# ProProject__led_2025-12-18.net
KiCad netlist of a schematic drawn in EasyEDA Pro
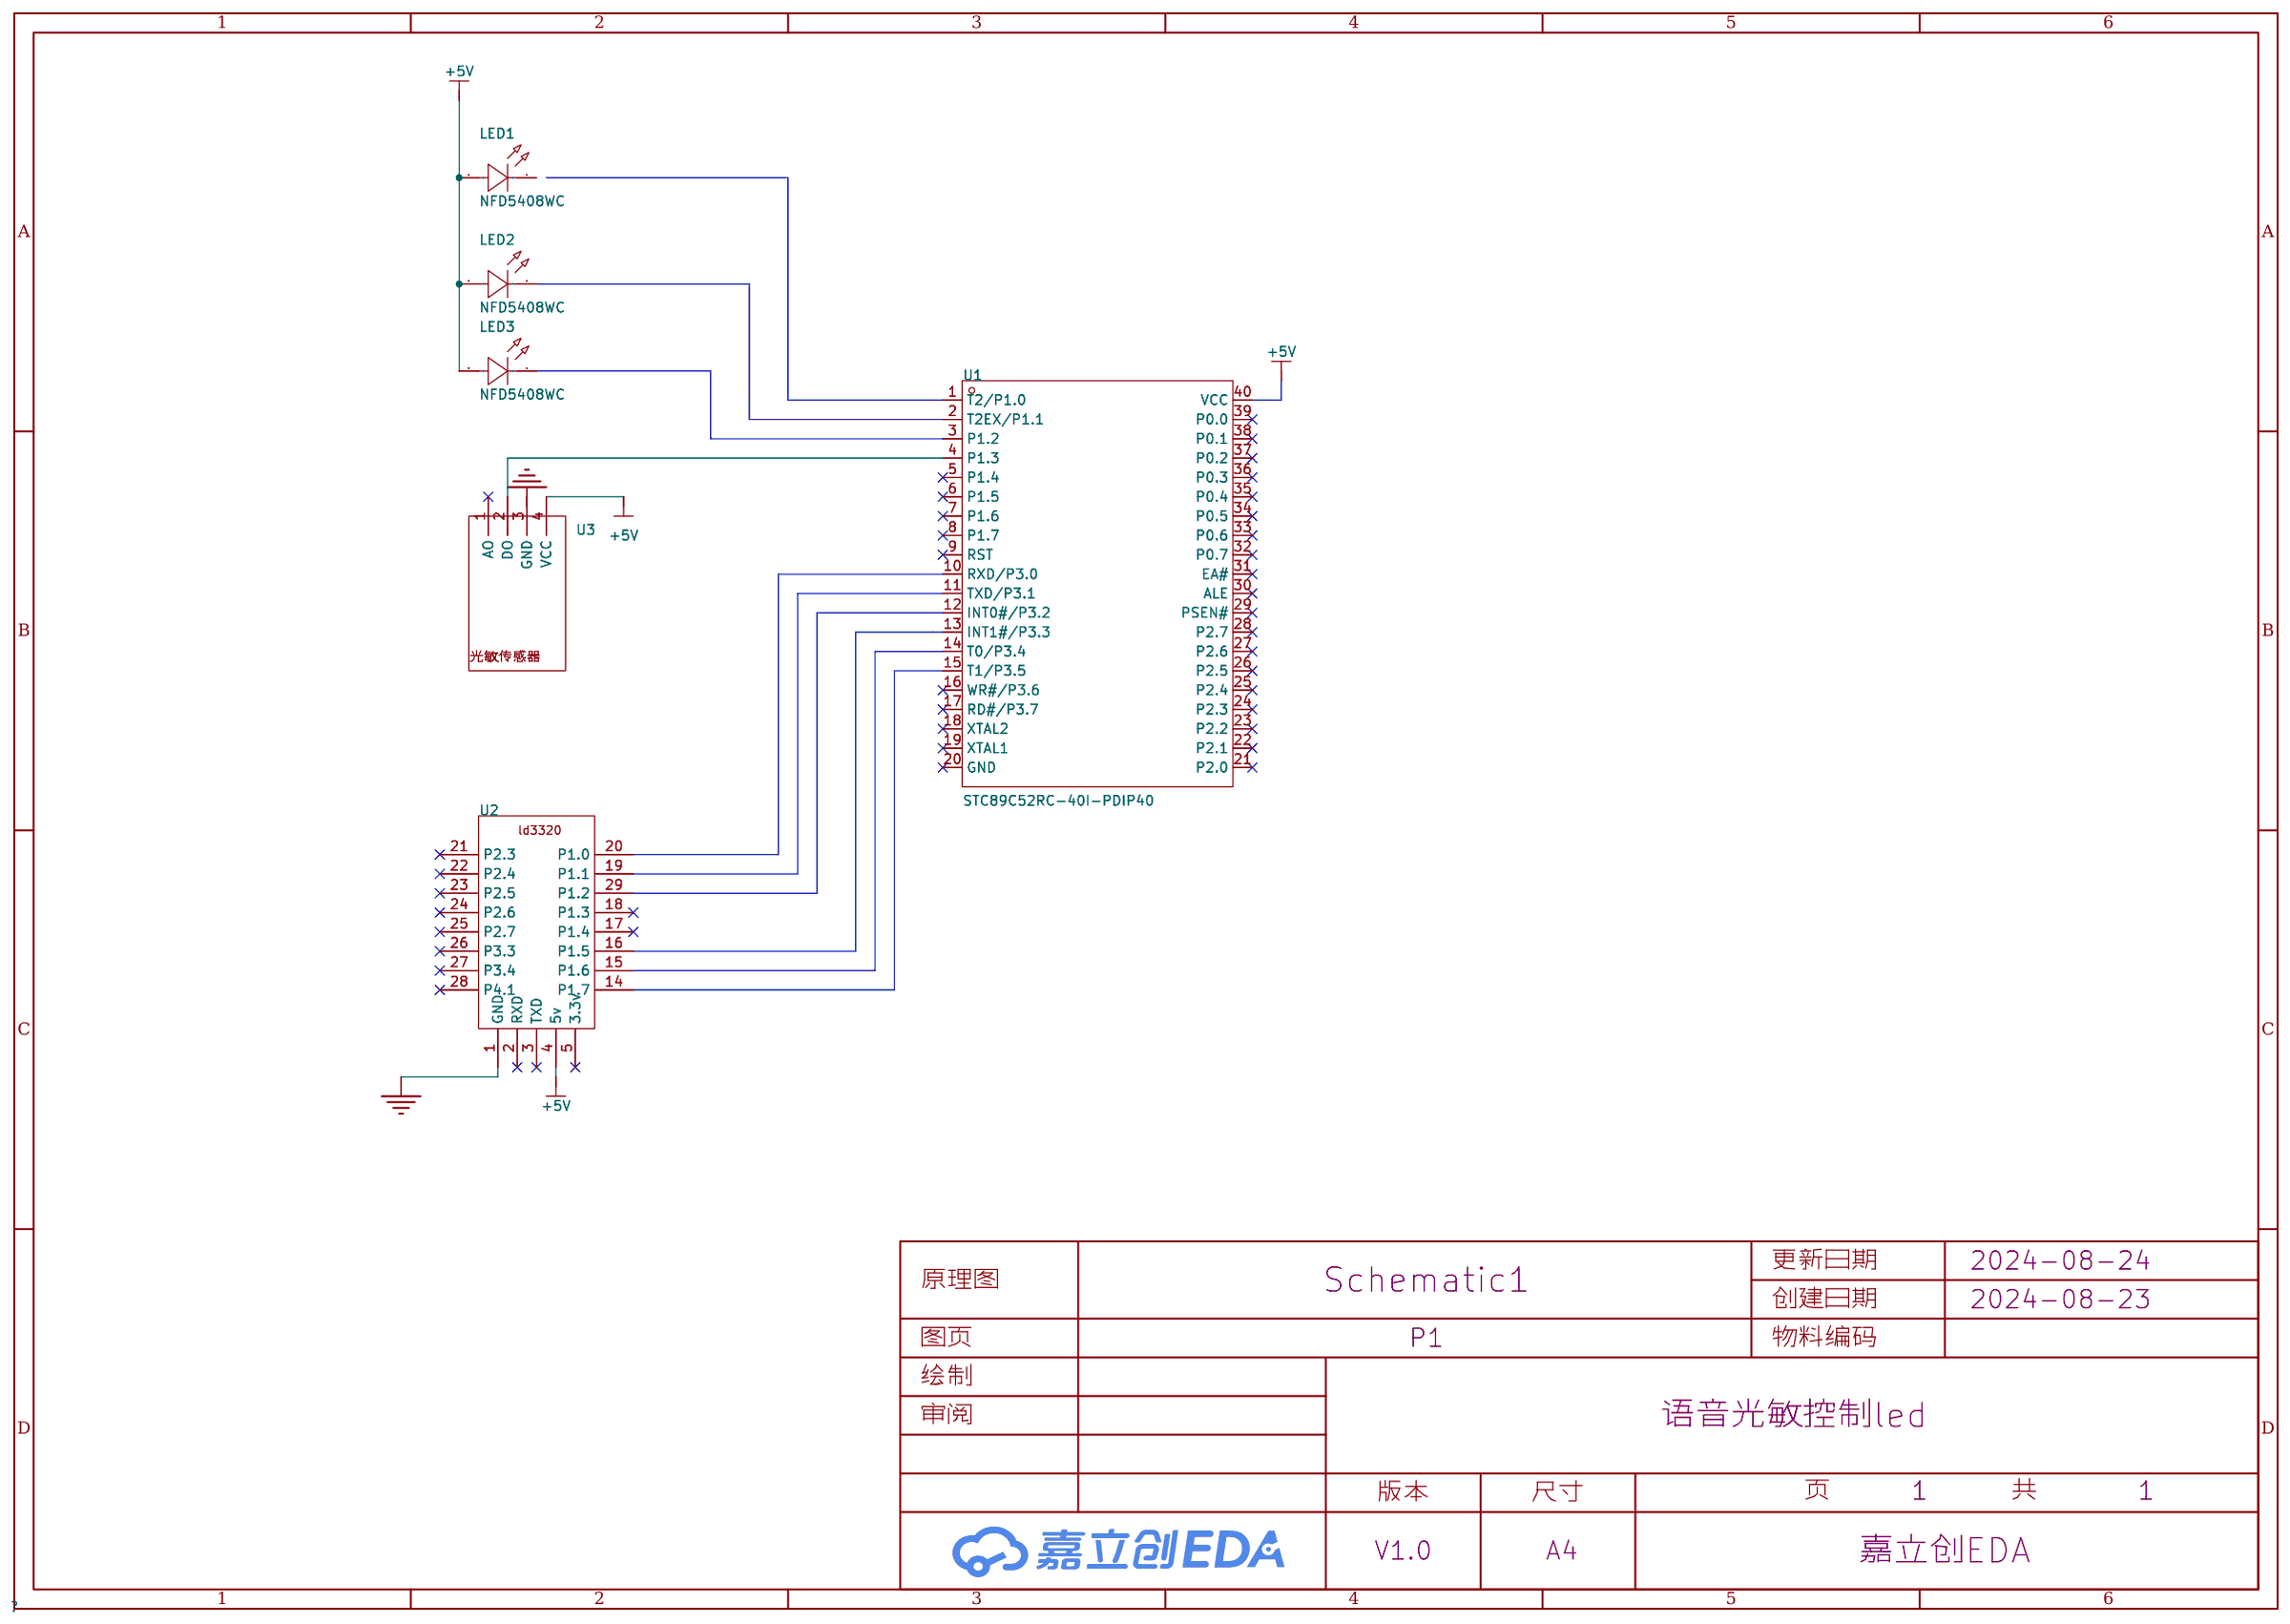
[diagram p0: schematic sheet]

(export (version "E")
  (design (tool "Eeschema 10.0.6"))
  (components
    (comp (ref "LED1")
      (value "NFD5408WC")
      (footprint "easyedapro:LED-TH_BD5.8-P2.54-RD")
      (description "发光颜色:白色;功率:200mW;发光角度:20°;工作温度:-30°C~+85°C;")
      (fields (field (name "Manufacturer") "国星光电"))
      (libsource (lib "easyedapro") (part "NFD5408WC"))
    )
    (comp (ref "LED2")
      (value "NFD5408WC")
      (footprint "easyedapro:LED-TH_BD5.8-P2.54-RD")
      (description "发光颜色:白色;功率:200mW;发光角度:20°;工作温度:-30°C~+85°C;")
      (fields (field (name "Manufacturer") "国星光电"))
      (libsource (lib "easyedapro") (part "NFD5408WC"))
    )
    (comp (ref "LED3")
      (value "NFD5408WC")
      (footprint "easyedapro:LED-TH_BD5.8-P2.54-RD")
      (description "发光颜色:白色;功率:200mW;发光角度:20°;工作温度:-30°C~+85°C;")
      (fields (field (name "Manufacturer") "国星光电"))
      (libsource (lib "easyedapro") (part "NFD5408WC"))
    )
    (comp (ref "U1")
      (value "STC89C52RC-40I-PDIP40")
      (footprint "easyedapro:DIP-40_L52.0-W13.7-P2.54-LS15.2-BL")
      (description "CPU内核:51系列;程序存储容量:8KB;RAM总容量:512Byte;GPIO端口数量:35;工作电压范围:3.3V~5.5V;CPU最大主频:-;程序存储器类型:FLASH;")
      (fields (field (name "Manufacturer") "STC(宏晶)"))
      (libsource (lib "easyedapro") (part "STC89C52RC-40I"))
    )
    (comp (ref "U2") (value "~") (libsource (lib "easyedapro") (part "LD3320")))
    (comp (ref "U3") (value "~") (libsource (lib "easyedapro") (part "光敏传感器")))
  )
  (nets
    (net (code "1") (name "+5V") (class "Default")
      (node (ref "LED1") (pin "2") (pinfunction "A_2") (pintype "unspecified"))
      (node (ref "LED2") (pin "2") (pinfunction "A_2") (pintype "unspecified"))
      (node (ref "LED3") (pin "2") (pinfunction "A_2") (pintype "unspecified"))
      (node (ref "U2") (pin "4") (pinfunction "5v_4") (pintype "input"))
      (node (ref "U3") (pin "4") (pinfunction "VCC_4") (pintype "input"))
    )
    (net (code "2") (name "GND") (class "Default")
      (node (ref "U2") (pin "1") (pinfunction "GND_1") (pintype "input"))
      (node (ref "U3") (pin "3") (pinfunction "GND_3") (pintype "input"))
    )
    (net (code "3") (name "Net-(U1-P1.3)") (class "Default")
      (node (ref "U1") (pin "4") (pinfunction "P1.3_4") (pintype "unspecified"))
      (node (ref "U3") (pin "2") (pinfunction "DO_2") (pintype "input"))
    )
    (net (code "4") (name "unconnected-(LED1-K-Pad1)") (class "Default")
      (node (ref "LED1") (pin "1") (pinfunction "K_1") (pintype "unspecified"))
    )
    (net (code "5") (name "unconnected-(LED2-K-Pad1)") (class "Default")
      (node (ref "LED2") (pin "1") (pinfunction "K_1") (pintype "unspecified"))
    )
    (net (code "6") (name "unconnected-(LED3-K-Pad1)") (class "Default")
      (node (ref "LED3") (pin "1") (pinfunction "K_1") (pintype "unspecified"))
    )
    (net (code "7") (name "unconnected-(U1-ALE-Pad30)") (class "Default")
      (node (ref "U1") (pin "30") (pinfunction "ALE_30") (pintype "unspecified+no_connect"))
    )
    (net (code "8") (name "unconnected-(U1-EA#-Pad31)") (class "Default")
      (node (ref "U1") (pin "31") (pinfunction "EA#_31") (pintype "unspecified+no_connect"))
    )
    (net (code "9") (name "unconnected-(U1-GND-Pad20)") (class "Default")
      (node (ref "U1") (pin "20") (pinfunction "GND_20") (pintype "unspecified+no_connect"))
    )
    (net (code "10") (name "unconnected-(U1-INT0#{slash}P3.2-Pad12)") (class "Default")
      (node (ref "U1") (pin "12") (pinfunction "INT0#/P3.2_12") (pintype "unspecified"))
    )
    (net (code "11") (name "unconnected-(U1-INT1#{slash}P3.3-Pad13)") (class "Default")
      (node (ref "U1") (pin "13") (pinfunction "INT1#/P3.3_13") (pintype "unspecified"))
    )
    (net (code "12") (name "unconnected-(U1-P0.0-Pad39)") (class "Default")
      (node (ref "U1") (pin "39") (pinfunction "P0.0_39") (pintype "unspecified+no_connect"))
    )
    (net (code "13") (name "unconnected-(U1-P0.1-Pad38)") (class "Default")
      (node (ref "U1") (pin "38") (pinfunction "P0.1_38") (pintype "unspecified+no_connect"))
    )
    (net (code "14") (name "unconnected-(U1-P0.2-Pad37)") (class "Default")
      (node (ref "U1") (pin "37") (pinfunction "P0.2_37") (pintype "unspecified+no_connect"))
    )
    (net (code "15") (name "unconnected-(U1-P0.3-Pad36)") (class "Default")
      (node (ref "U1") (pin "36") (pinfunction "P0.3_36") (pintype "unspecified+no_connect"))
    )
    (net (code "16") (name "unconnected-(U1-P0.4-Pad35)") (class "Default")
      (node (ref "U1") (pin "35") (pinfunction "P0.4_35") (pintype "unspecified+no_connect"))
    )
    (net (code "17") (name "unconnected-(U1-P0.5-Pad34)") (class "Default")
      (node (ref "U1") (pin "34") (pinfunction "P0.5_34") (pintype "unspecified+no_connect"))
    )
    (net (code "18") (name "unconnected-(U1-P0.6-Pad33)") (class "Default")
      (node (ref "U1") (pin "33") (pinfunction "P0.6_33") (pintype "unspecified+no_connect"))
    )
    (net (code "19") (name "unconnected-(U1-P0.7-Pad32)") (class "Default")
      (node (ref "U1") (pin "32") (pinfunction "P0.7_32") (pintype "unspecified+no_connect"))
    )
    (net (code "20") (name "unconnected-(U1-P1.2-Pad3)") (class "Default")
      (node (ref "U1") (pin "3") (pinfunction "P1.2_3") (pintype "unspecified"))
    )
    (net (code "21") (name "unconnected-(U1-P1.4-Pad5)") (class "Default")
      (node (ref "U1") (pin "5") (pinfunction "P1.4_5") (pintype "unspecified+no_connect"))
    )
    (net (code "22") (name "unconnected-(U1-P1.5-Pad6)") (class "Default")
      (node (ref "U1") (pin "6") (pinfunction "P1.5_6") (pintype "unspecified+no_connect"))
    )
    (net (code "23") (name "unconnected-(U1-P1.6-Pad7)") (class "Default")
      (node (ref "U1") (pin "7") (pinfunction "P1.6_7") (pintype "unspecified+no_connect"))
    )
    (net (code "24") (name "unconnected-(U1-P1.7-Pad8)") (class "Default")
      (node (ref "U1") (pin "8") (pinfunction "P1.7_8") (pintype "unspecified+no_connect"))
    )
    (net (code "25") (name "unconnected-(U1-P2.0-Pad21)") (class "Default")
      (node (ref "U1") (pin "21") (pinfunction "P2.0_21") (pintype "unspecified+no_connect"))
    )
    (net (code "26") (name "unconnected-(U1-P2.1-Pad22)") (class "Default")
      (node (ref "U1") (pin "22") (pinfunction "P2.1_22") (pintype "unspecified+no_connect"))
    )
    (net (code "27") (name "unconnected-(U1-P2.2-Pad23)") (class "Default")
      (node (ref "U1") (pin "23") (pinfunction "P2.2_23") (pintype "unspecified+no_connect"))
    )
    (net (code "28") (name "unconnected-(U1-P2.3-Pad24)") (class "Default")
      (node (ref "U1") (pin "24") (pinfunction "P2.3_24") (pintype "unspecified+no_connect"))
    )
    (net (code "29") (name "unconnected-(U1-P2.4-Pad25)") (class "Default")
      (node (ref "U1") (pin "25") (pinfunction "P2.4_25") (pintype "unspecified+no_connect"))
    )
    (net (code "30") (name "unconnected-(U1-P2.5-Pad26)") (class "Default")
      (node (ref "U1") (pin "26") (pinfunction "P2.5_26") (pintype "unspecified+no_connect"))
    )
    (net (code "31") (name "unconnected-(U1-P2.6-Pad27)") (class "Default")
      (node (ref "U1") (pin "27") (pinfunction "P2.6_27") (pintype "unspecified+no_connect"))
    )
    (net (code "32") (name "unconnected-(U1-P2.7-Pad28)") (class "Default")
      (node (ref "U1") (pin "28") (pinfunction "P2.7_28") (pintype "unspecified+no_connect"))
    )
    (net (code "33") (name "unconnected-(U1-PSEN#-Pad29)") (class "Default")
      (node (ref "U1") (pin "29") (pinfunction "PSEN#_29") (pintype "unspecified+no_connect"))
    )
    (net (code "34") (name "unconnected-(U1-RD#{slash}P3.7-Pad17)") (class "Default")
      (node (ref "U1") (pin "17") (pinfunction "RD#/P3.7_17") (pintype "unspecified+no_connect"))
    )
    (net (code "35") (name "unconnected-(U1-RST-Pad9)") (class "Default")
      (node (ref "U1") (pin "9") (pinfunction "RST_9") (pintype "unspecified+no_connect"))
    )
    (net (code "36") (name "unconnected-(U1-RXD{slash}P3.0-Pad10)") (class "Default")
      (node (ref "U1") (pin "10") (pinfunction "RXD/P3.0_10") (pintype "unspecified"))
    )
    (net (code "37") (name "unconnected-(U1-T0{slash}P3.4-Pad14)") (class "Default")
      (node (ref "U1") (pin "14") (pinfunction "T0/P3.4_14") (pintype "unspecified"))
    )
    (net (code "38") (name "unconnected-(U1-T1{slash}P3.5-Pad15)") (class "Default")
      (node (ref "U1") (pin "15") (pinfunction "T1/P3.5_15") (pintype "unspecified"))
    )
    (net (code "39") (name "unconnected-(U1-T2EX{slash}P1.1-Pad2)") (class "Default")
      (node (ref "U1") (pin "2") (pinfunction "T2EX/P1.1_2") (pintype "unspecified"))
    )
    (net (code "40") (name "unconnected-(U1-T2{slash}P1.0-Pad1)") (class "Default")
      (node (ref "U1") (pin "1") (pinfunction "T2/P1.0_1") (pintype "unspecified"))
    )
    (net (code "41") (name "unconnected-(U1-TXD{slash}P3.1-Pad11)") (class "Default")
      (node (ref "U1") (pin "11") (pinfunction "TXD/P3.1_11") (pintype "unspecified"))
    )
    (net (code "42") (name "unconnected-(U1-VCC-Pad40)") (class "Default")
      (node (ref "U1") (pin "40") (pinfunction "VCC_40") (pintype "unspecified"))
    )
    (net (code "43") (name "unconnected-(U1-WR#{slash}P3.6-Pad16)") (class "Default")
      (node (ref "U1") (pin "16") (pinfunction "WR#/P3.6_16") (pintype "unspecified+no_connect"))
    )
    (net (code "44") (name "unconnected-(U1-XTAL1-Pad19)") (class "Default")
      (node (ref "U1") (pin "19") (pinfunction "XTAL1_19") (pintype "unspecified+no_connect"))
    )
    (net (code "45") (name "unconnected-(U1-XTAL2-Pad18)") (class "Default")
      (node (ref "U1") (pin "18") (pinfunction "XTAL2_18") (pintype "unspecified+no_connect"))
    )
    (net (code "46") (name "unconnected-(U2-3.3v-Pad5)") (class "Default")
      (node (ref "U2") (pin "5") (pinfunction "3.3v_5") (pintype "input+no_connect"))
    )
    (net (code "47") (name "unconnected-(U2-P1.0-Pad20)") (class "Default")
      (node (ref "U2") (pin "20") (pinfunction "P1.0_20") (pintype "input"))
    )
    (net (code "48") (name "unconnected-(U2-P1.1-Pad19)") (class "Default")
      (node (ref "U2") (pin "19") (pinfunction "P1.1_19") (pintype "input"))
    )
    (net (code "49") (name "unconnected-(U2-P1.2-Pad29)") (class "Default")
      (node (ref "U2") (pin "29") (pinfunction "P1.2_29") (pintype "input"))
    )
    (net (code "50") (name "unconnected-(U2-P1.3-Pad18)") (class "Default")
      (node (ref "U2") (pin "18") (pinfunction "P1.3_18") (pintype "input+no_connect"))
    )
    (net (code "51") (name "unconnected-(U2-P1.4-Pad17)") (class "Default")
      (node (ref "U2") (pin "17") (pinfunction "P1.4_17") (pintype "input+no_connect"))
    )
    (net (code "52") (name "unconnected-(U2-P1.5-Pad16)") (class "Default")
      (node (ref "U2") (pin "16") (pinfunction "P1.5_16") (pintype "input"))
    )
    (net (code "53") (name "unconnected-(U2-P1.6-Pad15)") (class "Default")
      (node (ref "U2") (pin "15") (pinfunction "P1.6_15") (pintype "input"))
    )
    (net (code "54") (name "unconnected-(U2-P1.7-Pad14)") (class "Default")
      (node (ref "U2") (pin "14") (pinfunction "P1.7_14") (pintype "input"))
    )
    (net (code "55") (name "unconnected-(U2-P2.3-Pad21)") (class "Default")
      (node (ref "U2") (pin "21") (pinfunction "P2.3_21") (pintype "input+no_connect"))
    )
    (net (code "56") (name "unconnected-(U2-P2.4-Pad22)") (class "Default")
      (node (ref "U2") (pin "22") (pinfunction "P2.4_22") (pintype "input+no_connect"))
    )
    (net (code "57") (name "unconnected-(U2-P2.5-Pad23)") (class "Default")
      (node (ref "U2") (pin "23") (pinfunction "P2.5_23") (pintype "input+no_connect"))
    )
    (net (code "58") (name "unconnected-(U2-P2.6-Pad24)") (class "Default")
      (node (ref "U2") (pin "24") (pinfunction "P2.6_24") (pintype "input+no_connect"))
    )
    (net (code "59") (name "unconnected-(U2-P2.7-Pad25)") (class "Default")
      (node (ref "U2") (pin "25") (pinfunction "P2.7_25") (pintype "input+no_connect"))
    )
    (net (code "60") (name "unconnected-(U2-P3.3-Pad26)") (class "Default")
      (node (ref "U2") (pin "26") (pinfunction "P3.3_26") (pintype "input+no_connect"))
    )
    (net (code "61") (name "unconnected-(U2-P3.4-Pad27)") (class "Default")
      (node (ref "U2") (pin "27") (pinfunction "P3.4_27") (pintype "input+no_connect"))
    )
    (net (code "62") (name "unconnected-(U2-P4.1-Pad28)") (class "Default")
      (node (ref "U2") (pin "28") (pinfunction "P4.1_28") (pintype "input+no_connect"))
    )
    (net (code "63") (name "unconnected-(U2-RXD-Pad2)") (class "Default")
      (node (ref "U2") (pin "2") (pinfunction "RXD_2") (pintype "input+no_connect"))
    )
    (net (code "64") (name "unconnected-(U2-TXD-Pad3)") (class "Default")
      (node (ref "U2") (pin "3") (pinfunction "TXD_3") (pintype "input+no_connect"))
    )
    (net (code "65") (name "unconnected-(U3-AO-Pad1)") (class "Default")
      (node (ref "U3") (pin "1") (pinfunction "AO_1") (pintype "input+no_connect"))
    )
  )
)
